# design.net
KiCad netlist of a schematic drawn in Altium Designer
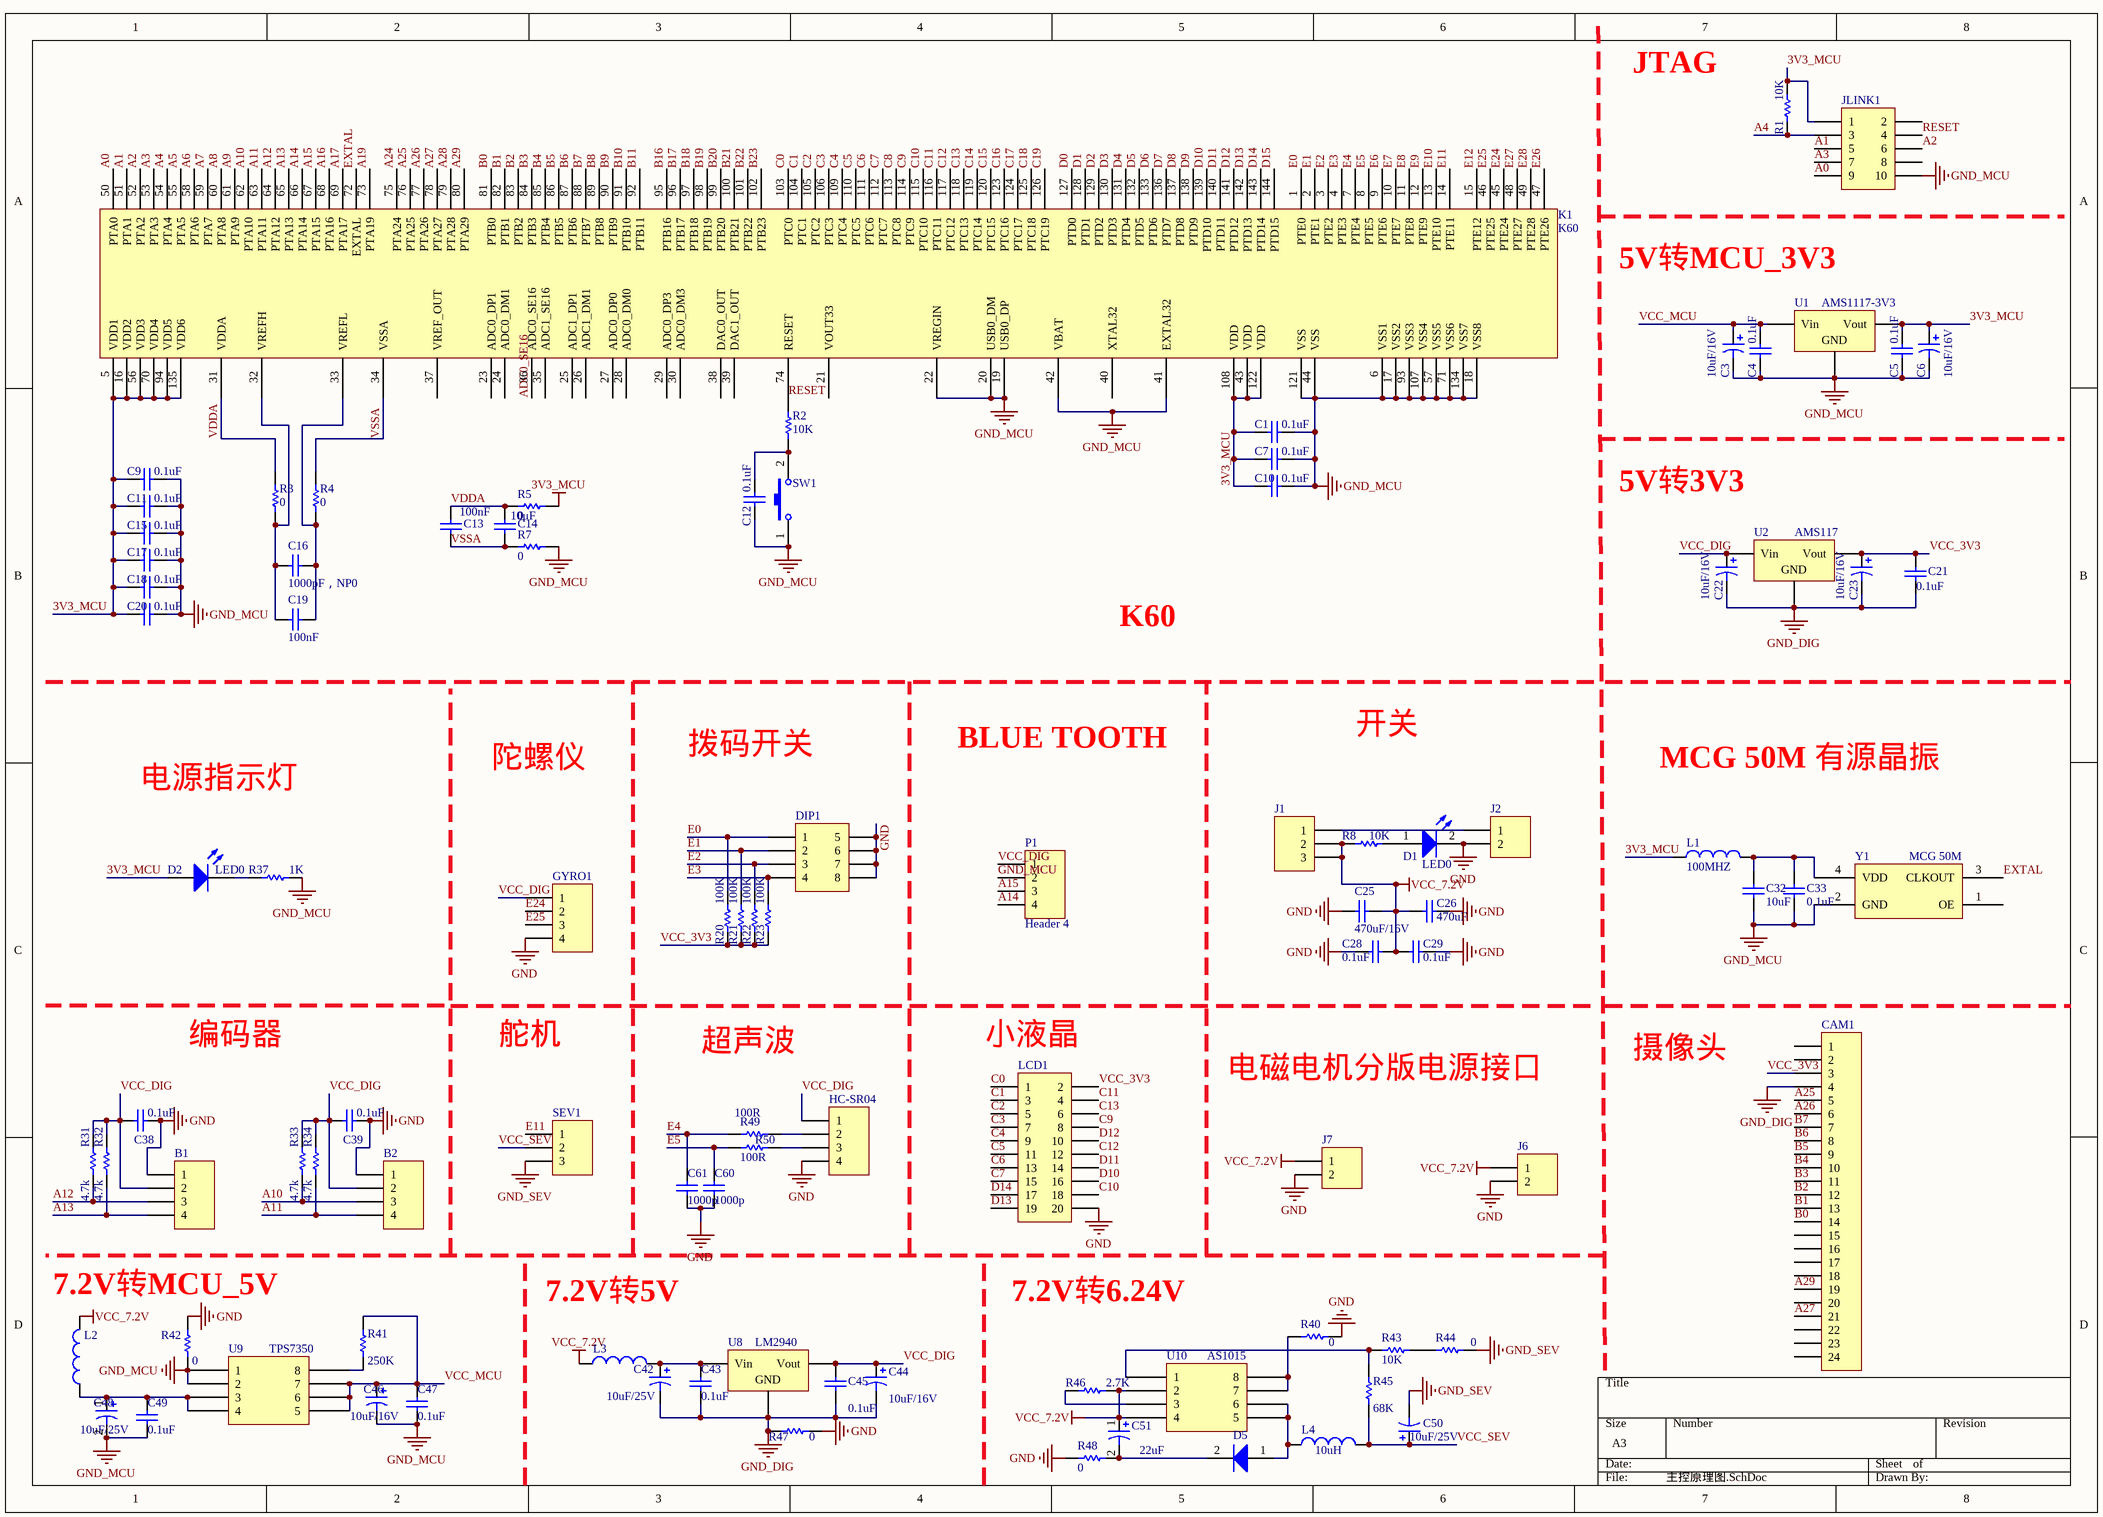
[diagram p0: 主控原理图.SchDoc]

(export (version "E")
  (design (tool "Eeschema 10.0.6"))
  (components
    (comp (ref "B1")
      (value "MHDR1X4")
      (footprint "3PIN-2.54")
      (description "Header, 4-Pin")
      (fields (field (name "PUBLISHER") "Altium Limited"))
      (libsource (lib "Miscellaneous Connectors") (part "MHDR1X4"))
    )
    (comp (ref "B2")
      (value "MHDR1X4")
      (footprint "3PIN-2.54")
      (description "Header, 4-Pin")
      (fields (field (name "PUBLISHER") "Altium Limited"))
      (libsource (lib "Miscellaneous Connectors") (part "MHDR1X4"))
    )
    (comp (ref "C1")
      (value "0.1uF")
      (footprint "c0805")
      (description "Capacitor")
      (fields (field (name "PUBLISHER") "Altium Limited"))
      (libsource (lib "Miscellaneous Devices") (part "Cap"))
    )
    (comp (ref "C3")
      (value "10uF/16V")
      (footprint "C1206")
      (description "Polarized Capacitor (Radial)")
      (fields (field (name "PUBLISHER") "Altium Limited"))
      (libsource (lib "") (part "Cap Pol1_1"))
    )
    (comp (ref "C4")
      (value "0.1uF")
      (footprint "c0805")
      (description "Capacitor")
      (fields (field (name "PUBLISHER") "Altium Limited"))
      (libsource (lib "Miscellaneous Devices") (part "Cap"))
    )
    (comp (ref "C5")
      (value "0.1uF")
      (footprint "c0805")
      (description "Capacitor")
      (fields (field (name "PUBLISHER") "Altium Limited"))
      (libsource (lib "Miscellaneous Devices") (part "Cap"))
    )
    (comp (ref "C6")
      (value "10uF/16V")
      (footprint "C1206")
      (description "Polarized Capacitor (Radial)")
      (fields (field (name "PUBLISHER") "Altium Limited"))
      (libsource (lib "") (part "Cap Pol1_1"))
    )
    (comp (ref "C7")
      (value "0.1uF")
      (footprint "c0805")
      (description "Capacitor")
      (fields (field (name "PUBLISHER") "Altium Limited"))
      (libsource (lib "Miscellaneous Devices") (part "Cap"))
    )
    (comp (ref "C9")
      (value "0.1uF")
      (footprint "c0805")
      (description "Capacitor")
      (fields (field (name "PUBLISHER") "Altium Limited"))
      (libsource (lib "Miscellaneous Devices") (part "Cap"))
    )
    (comp (ref "C10")
      (value "0.1uF")
      (footprint "c0805")
      (description "Capacitor")
      (fields (field (name "PUBLISHER") "Altium Limited"))
      (libsource (lib "Miscellaneous Devices") (part "Cap"))
    )
    (comp (ref "C11")
      (value "0.1uF")
      (footprint "c0805")
      (description "Capacitor")
      (fields (field (name "PUBLISHER") "Altium Limited"))
      (libsource (lib "Miscellaneous Devices") (part "Cap"))
    )
    (comp (ref "C12")
      (value "0.1uF")
      (footprint "c0805")
      (description "Capacitor")
      (fields (field (name "PUBLISHER") "Altium Limited"))
      (libsource (lib "Miscellaneous Devices") (part "Cap"))
    )
    (comp (ref "C13")
      (value "100nF")
      (footprint "C0805")
      (description "Capacitor (Semiconductor SIM Model)")
      (fields (field (name "Comment") "Cap Semi") (field (name "PUBLISHER") "Altium Limited"))
      (libsource (lib "Miscellaneous Devices") (part "Cap Semi"))
    )
    (comp (ref "C14")
      (value "10μF")
      (footprint "C0805")
      (description "Capacitor (Semiconductor SIM Model)")
      (fields (field (name "PUBLISHER") "Altium Limited"))
      (libsource (lib "Miscellaneous Devices") (part "Cap Semi"))
    )
    (comp (ref "C15")
      (value "0.1uF")
      (footprint "c0805")
      (description "Capacitor")
      (fields (field (name "PUBLISHER") "Altium Limited"))
      (libsource (lib "Miscellaneous Devices") (part "Cap"))
    )
    (comp (ref "C16")
      (value "1000pF，NP0")
      (footprint "C0805")
      (description "Capacitor (Semiconductor SIM Model)")
      (fields (field (name "Comment") "Cap Semi") (field (name "PUBLISHER") "Altium Limited"))
      (libsource (lib "Miscellaneous Devices") (part "Cap Semi"))
    )
    (comp (ref "C17")
      (value "0.1uF")
      (footprint "c0805")
      (description "Capacitor")
      (fields (field (name "PUBLISHER") "Altium Limited"))
      (libsource (lib "Miscellaneous Devices") (part "Cap"))
    )
    (comp (ref "C18")
      (value "0.1uF")
      (footprint "c0805")
      (description "Capacitor")
      (fields (field (name "PUBLISHER") "Altium Limited"))
      (libsource (lib "Miscellaneous Devices") (part "Cap"))
    )
    (comp (ref "C19")
      (value "100nF")
      (footprint "C0805")
      (description "Capacitor (Semiconductor SIM Model)")
      (fields (field (name "Comment") "Cap Semi") (field (name "PUBLISHER") "Altium Limited"))
      (libsource (lib "Miscellaneous Devices") (part "Cap Semi"))
    )
    (comp (ref "C20")
      (value "0.1uF")
      (footprint "c0805")
      (description "Capacitor")
      (fields (field (name "PUBLISHER") "Altium Limited"))
      (libsource (lib "Miscellaneous Devices") (part "Cap"))
    )
    (comp (ref "C21")
      (value "0.1uF")
      (footprint "C0805")
      (description "Capacitor")
      (fields (field (name "PUBLISHER") "Altium Limited"))
      (libsource (lib "Miscellaneous Devices") (part "Cap"))
    )
    (comp (ref "C22")
      (value "10uF/16V")
      (footprint "C1206")
      (description "Polarized Capacitor (Radial)")
      (fields (field (name "PUBLISHER") "Altium Limited"))
      (libsource (lib "") (part "Cap Pol1_1"))
    )
    (comp (ref "C23")
      (value "10uF/16V")
      (footprint "C1206")
      (description "Polarized Capacitor (Radial)")
      (fields (field (name "PUBLISHER") "Altium Limited"))
      (libsource (lib "") (part "Cap Pol1_1"))
    )
    (comp (ref "C25")
      (value "470uF/16V")
      (footprint "C8X8MM")
      (description "Capacitor")
      (fields (field (name "PUBLISHER") "Altium Limited"))
      (libsource (lib "Miscellaneous Devices") (part "Cap"))
    )
    (comp (ref "C26")
      (value "470uF")
      (footprint "C8X8MM")
      (description "Capacitor")
      (fields (field (name "Comment") "470uF/16V") (field (name "PUBLISHER") "Altium Limited"))
      (libsource (lib "Miscellaneous Devices") (part "Cap"))
    )
    (comp (ref "C28")
      (value "0.1uF")
      (footprint "C0805")
      (description "Capacitor")
      (fields (field (name "PUBLISHER") "Altium Limited"))
      (libsource (lib "Miscellaneous Devices") (part "Cap"))
    )
    (comp (ref "C29")
      (value "0.1uF")
      (footprint "C0805")
      (description "Capacitor")
      (fields (field (name "PUBLISHER") "Altium Limited"))
      (libsource (lib "Miscellaneous Devices") (part "Cap"))
    )
    (comp (ref "C32")
      (value "10uF")
      (footprint "c0805")
      (description "Capacitor")
      (fields (field (name "PUBLISHER") "Altium Limited"))
      (libsource (lib "Miscellaneous Devices") (part "Cap"))
    )
    (comp (ref "C33")
      (value "0.1uF")
      (footprint "c0805")
      (description "Capacitor")
      (fields (field (name "PUBLISHER") "Altium Limited"))
      (libsource (lib "Miscellaneous Devices") (part "Cap"))
    )
    (comp (ref "C38")
      (value "0.1uF")
      (footprint "C0805")
      (description "Capacitor")
      (fields (field (name "PUBLISHER") "Altium Limited"))
      (libsource (lib "Miscellaneous Devices") (part "Cap"))
    )
    (comp (ref "C39")
      (value "0.1uF")
      (footprint "C0805")
      (description "Capacitor")
      (fields (field (name "PUBLISHER") "Altium Limited"))
      (libsource (lib "Miscellaneous Devices") (part "Cap"))
    )
    (comp (ref "C42")
      (value "10uF/25V")
      (footprint "C1206")
      (description "Polarized Capacitor (Radial)")
      (fields (field (name "PUBLISHER") "Altium Limited"))
      (libsource (lib "") (part "Cap Pol1_1"))
    )
    (comp (ref "C43")
      (value "0.1uF")
      (footprint "C0805")
      (description "Capacitor")
      (fields (field (name "PUBLISHER") "Altium Limited"))
      (libsource (lib "Miscellaneous Devices") (part "Cap"))
    )
    (comp (ref "C44")
      (value "10uF/16V")
      (footprint "C1206")
      (description "Polarized Capacitor (Radial)")
      (fields (field (name "PUBLISHER") "Altium Limited"))
      (libsource (lib "") (part "Cap Pol1_1"))
    )
    (comp (ref "C45")
      (value "0.1uF")
      (footprint "C0805")
      (description "Capacitor")
      (fields (field (name "PUBLISHER") "Altium Limited"))
      (libsource (lib "Miscellaneous Devices") (part "Cap"))
    )
    (comp (ref "C46")
      (value "10uF/16V")
      (footprint "C1206")
      (description "Polarized Capacitor (Radial)")
      (fields (field (name "PUBLISHER") "Altium Limited"))
      (libsource (lib "") (part "Cap Pol1_1"))
    )
    (comp (ref "C47")
      (value "0.1uF")
      (footprint "C0805")
      (description "Capacitor")
      (fields (field (name "PUBLISHER") "Altium Limited"))
      (libsource (lib "Miscellaneous Devices") (part "Cap"))
    )
    (comp (ref "C48")
      (value "10uF/25V")
      (footprint "C1206")
      (description "Polarized Capacitor (Radial)")
      (fields (field (name "PUBLISHER") "Altium Limited"))
      (libsource (lib "Miscellaneous Devices") (part "Cap Pol1"))
    )
    (comp (ref "C49")
      (value "0.1uF")
      (footprint "C0805")
      (description "Capacitor")
      (fields (field (name "PUBLISHER") "Altium Limited"))
      (libsource (lib "Miscellaneous Devices") (part "Cap"))
    )
    (comp (ref "C50")
      (value "10uF/25V")
      (footprint "PCBComponent_1 - duplicate6")
      (description "Polarized Capacitor (Radial)")
      (fields (field (name "PUBLISHER") "Altium Limited"))
      (libsource (lib "") (part "Cap Pol1_1"))
    )
    (comp (ref "C51")
      (value "22uF")
      (footprint "CAP5X5")
      (description "Polarized Capacitor (Radial)")
      (fields (field (name "PUBLISHER") "Altium Limited"))
      (libsource (lib "Miscellaneous Devices") (part "Cap Pol1"))
    )
    (comp (ref "C60")
      (value "1000p")
      (footprint "C0805")
      (description "Capacitor")
      (fields (field (name "Comment") "0.1uF") (field (name "PUBLISHER") "Altium Limited"))
      (libsource (lib "Miscellaneous Devices") (part "Cap"))
    )
    (comp (ref "C61")
      (value "1000p")
      (footprint "C0805")
      (description "Capacitor")
      (fields (field (name "Comment") "0.1uF") (field (name "PUBLISHER") "Altium Limited"))
      (libsource (lib "Miscellaneous Devices") (part "Cap"))
    )
    (comp (ref "CAM1")
      (value "Header 24")
      (footprint "24PIN0.5MM软排座")
      (description "Header, 24-Pin")
      (fields (field (name "PUBLISHER") "Altium Limited"))
      (libsource (lib "Miscellaneous Connectors") (part "Header 24"))
    )
    (comp (ref "D1")
      (value "LED0")
      (footprint "d0603")
      (description "Typical INFRARED GaAs LED")
      (fields (field (name "PUBLISHER") "Altium Limited"))
      (libsource (lib "Miscellaneous Devices") (part "LED0"))
    )
    (comp (ref "D2")
      (value "LED0")
      (footprint "d0603")
      (description "Typical INFRARED GaAs LED")
      (fields (field (name "PUBLISHER") "Altium Limited"))
      (libsource (lib "") (part "LED0_1"))
    )
    (comp (ref "D5")
      (value "Diode 1N914")
      (footprint "四代目:SMA")
      (description "High Conductance Fast Diode")
      (fields (field (name "PUBLISHER") "Altium Limited"))
      (libsource (lib "Miscellaneous Devices") (part "Diode 1N914"))
    )
    (comp (ref "DIP1")
      (value "Header 4X2")
      (footprint "PCBComponent_1 - duplicate1")
      (description "Header, 4-Pin, Dual row")
      (fields (field (name "PUBLISHER") "Altium Limited"))
      (libsource (lib "Miscellaneous Connectors") (part "Header 4X2"))
    )
    (comp (ref "GYRO1")
      (value "Header 4")
      (footprint "tly")
      (description "Header, 4-Pin")
      (fields (field (name "PUBLISHER") "Altium Limited"))
      (libsource (lib "Miscellaneous Connectors") (part "Header 4"))
    )
    (comp (ref "HC-SR04")
      (value "Header 4")
      (footprint "SIP4")
      (description "Header, 4-Pin")
      (fields (field (name "PUBLISHER") "Altium Limited"))
      (libsource (lib "Miscellaneous Connectors") (part "Header 4"))
    )
    (comp (ref "J1")
      (value "Header 3")
      (footprint "7.2")
      (description "Header, 3-Pin")
      (fields (field (name "PUBLISHER") "Altium Limited"))
      (libsource (lib "") (part "Header 3_1"))
    )
    (comp (ref "J2")
      (value "Header 2")
      (footprint "PCBComponent_1 - duplicate5")
      (description "Header, 2-Pin")
      (fields (field (name "PUBLISHER") "Altium Limited"))
      (libsource (lib "Miscellaneous Connectors") (part "Header 2"))
    )
    (comp (ref "J6")
      (value "Header 2")
      (footprint "PCBComponent_1 - duplicate5")
      (description "Header, 2-Pin")
      (fields (field (name "PUBLISHER") "Altium Limited"))
      (libsource (lib "Miscellaneous Connectors") (part "Header 2"))
    )
    (comp (ref "J7")
      (value "Header 2")
      (footprint "PCBComponent_1 - duplicate5")
      (description "Header, 2-Pin")
      (fields (field (name "PUBLISHER") "Altium Limited"))
      (libsource (lib "Miscellaneous Connectors") (part "Header 2"))
    )
    (comp (ref "JLINK1")
      (value "Header 5X2")
      (footprint "HDR2X5")
      (description "Header, 5-Pin, Dual row")
      (fields (field (name "PUBLISHER") "Altium Limited"))
      (libsource (lib "Miscellaneous Connectors") (part "Header 5X2"))
    )
    (comp (ref "K1") (value "K60") (footprint "K60_QFP144") (libsource (lib "K60") (part "Component_1")))
    (comp (ref "L1")
      (value "100MHZ")
      (footprint "l0805")
      (description "Inductor")
      (fields (field (name "PUBLISHER") "Altium Limited"))
      (libsource (lib "Miscellaneous Devices") (part "Inductor"))
    )
    (comp (ref "L2")
      (value "~")
      (footprint "L0805")
      (description "Inductor")
      (fields (field (name "PUBLISHER") "Altium Limited"))
      (libsource (lib "Miscellaneous Devices") (part "Inductor"))
    )
    (comp (ref "L3")
      (value "Inductor")
      (footprint "L0805")
      (fields (field (name "PUBLISHER") "Altium Limited"))
      (libsource (lib "Miscellaneous Devices") (part "Inductor"))
    )
    (comp (ref "L4")
      (value "10uH")
      (footprint "电感7x7")
      (description "Inductor")
      (fields (field (name "PUBLISHER") "Altium Limited"))
      (libsource (lib "Miscellaneous Devices") (part "Inductor"))
    )
    (comp (ref "LCD1")
      (value "Header 10X2")
      (footprint "HDR2X10")
      (description "Header, 10-Pin, Dual row")
      (fields (field (name "PUBLISHER") "Altium Limited"))
      (libsource (lib "Miscellaneous Connectors") (part "Header 10X2"))
    )
    (comp (ref "P1")
      (value "Header 4")
      (footprint "HDR1X4")
      (description "Header, 4-Pin")
      (fields (field (name "PUBLISHER") "Altium Limited"))
      (libsource (lib "Miscellaneous Connectors") (part "Header 4"))
    )
    (comp (ref "R1")
      (value "10K")
      (footprint "R0805")
      (description "Resistor")
      (fields (field (name "PUBLISHER") "Altium Limited"))
      (libsource (lib "Miscellaneous Devices") (part "Res1"))
    )
    (comp (ref "R2")
      (value "10K")
      (footprint "r0805")
      (description "Resistor")
      (fields (field (name "PUBLISHER") "Altium Limited"))
      (libsource (lib "Miscellaneous Devices") (part "Res1"))
    )
    (comp (ref "R3")
      (value "0")
      (footprint "R0805")
      (description "Resistor")
      (fields (field (name "PUBLISHER") "Altium Limited"))
      (libsource (lib "Miscellaneous Devices") (part "Res1"))
    )
    (comp (ref "R4")
      (value "0")
      (footprint "R0805")
      (description "Resistor")
      (fields (field (name "PUBLISHER") "Altium Limited"))
      (libsource (lib "Miscellaneous Devices") (part "Res1"))
    )
    (comp (ref "R5")
      (value "0")
      (footprint "R0805")
      (description "Resistor")
      (fields (field (name "PUBLISHER") "Altium Limited"))
      (libsource (lib "Miscellaneous Devices") (part "Res1"))
    )
    (comp (ref "R7")
      (value "0")
      (footprint "R0805")
      (description "Resistor")
      (fields (field (name "PUBLISHER") "Altium Limited"))
      (libsource (lib "Miscellaneous Devices") (part "Res1"))
    )
    (comp (ref "R8")
      (value "10K")
      (footprint "R0805")
      (description "Resistor")
      (fields (field (name "Comment") "Res1") (field (name "PUBLISHER") "Altium Limited"))
      (libsource (lib "Miscellaneous Devices") (part "Res1"))
    )
    (comp (ref "R20")
      (value "100K")
      (footprint "R0805")
      (description "Resistor")
      (fields (field (name "PUBLISHER") "Altium Limited"))
      (libsource (lib "Miscellaneous Devices") (part "Res1"))
    )
    (comp (ref "R21")
      (value "100K")
      (footprint "R0805")
      (description "Resistor")
      (fields (field (name "PUBLISHER") "Altium Limited"))
      (libsource (lib "Miscellaneous Devices") (part "Res1"))
    )
    (comp (ref "R22")
      (value "100K")
      (footprint "R0805")
      (description "Resistor")
      (fields (field (name "PUBLISHER") "Altium Limited"))
      (libsource (lib "Miscellaneous Devices") (part "Res1"))
    )
    (comp (ref "R23")
      (value "100K")
      (footprint "R0805")
      (description "Resistor")
      (fields (field (name "PUBLISHER") "Altium Limited"))
      (libsource (lib "Miscellaneous Devices") (part "Res1"))
    )
    (comp (ref "R31")
      (value "4.7k")
      (footprint "R0805")
      (description "Resistor")
      (fields (field (name "Comment") "4.7K") (field (name "PUBLISHER") "Altium Limited"))
      (libsource (lib "Miscellaneous Devices") (part "Res1"))
    )
    (comp (ref "R32")
      (value "4.7k")
      (footprint "R0805")
      (description "Resistor")
      (fields (field (name "Comment") "4.7K") (field (name "PUBLISHER") "Altium Limited"))
      (libsource (lib "Miscellaneous Devices") (part "Res1"))
    )
    (comp (ref "R33")
      (value "4.7k")
      (footprint "R0805")
      (description "Resistor")
      (fields (field (name "Comment") "4.7K") (field (name "PUBLISHER") "Altium Limited"))
      (libsource (lib "Miscellaneous Devices") (part "Res1"))
    )
    (comp (ref "R34")
      (value "4.7k")
      (footprint "R0805")
      (description "Resistor")
      (fields (field (name "Comment") "4.7K") (field (name "PUBLISHER") "Altium Limited"))
      (libsource (lib "Miscellaneous Devices") (part "Res1"))
    )
    (comp (ref "R37")
      (value "1K")
      (footprint "R0805")
      (description "Resistor")
      (fields (field (name "PUBLISHER") "Altium Limited"))
      (libsource (lib "Miscellaneous Devices") (part "Res1"))
    )
    (comp (ref "R40")
      (value "0")
      (footprint "R0805")
      (description "Resistor")
      (fields (field (name "PUBLISHER") "Altium Limited"))
      (libsource (lib "Miscellaneous Devices") (part "Res1"))
    )
    (comp (ref "R41")
      (value "250K")
      (footprint "R0805")
      (description "Resistor")
      (fields (field (name "PUBLISHER") "Altium Limited"))
      (libsource (lib "Miscellaneous Devices") (part "Res1"))
    )
    (comp (ref "R42")
      (value "0")
      (footprint "R0805")
      (description "Resistor")
      (fields (field (name "PUBLISHER") "Altium Limited"))
      (libsource (lib "Miscellaneous Devices") (part "Res1"))
    )
    (comp (ref "R43")
      (value "10K")
      (footprint "R0805")
      (description "Resistor")
      (fields (field (name "PUBLISHER") "Altium Limited"))
      (libsource (lib "Miscellaneous Devices") (part "Res1"))
    )
    (comp (ref "R44")
      (value "0")
      (footprint "R0805")
      (description "Resistor")
      (fields (field (name "PUBLISHER") "Altium Limited"))
      (libsource (lib "Miscellaneous Devices") (part "Res1"))
    )
    (comp (ref "R45")
      (value "68K")
      (footprint "R0805")
      (description "Resistor")
      (fields (field (name "PUBLISHER") "Altium Limited"))
      (libsource (lib "Miscellaneous Devices") (part "Res1"))
    )
    (comp (ref "R46")
      (value "2.7K")
      (footprint "R0805")
      (description "Resistor")
      (fields (field (name "PUBLISHER") "Altium Limited"))
      (libsource (lib "Miscellaneous Devices") (part "Res1"))
    )
    (comp (ref "R47")
      (value "0")
      (footprint "R0805")
      (description "Resistor")
      (fields (field (name "PUBLISHER") "Altium Limited"))
      (libsource (lib "Miscellaneous Devices") (part "Res1"))
    )
    (comp (ref "R48")
      (value "0")
      (footprint "R0805")
      (description "Resistor")
      (fields (field (name "PUBLISHER") "Altium Limited"))
      (libsource (lib "Miscellaneous Devices") (part "Res1"))
    )
    (comp (ref "R49")
      (value "100R")
      (footprint "R0805")
      (description "Resistor")
      (fields (field (name "Comment") "100K") (field (name "PUBLISHER") "Altium Limited"))
      (libsource (lib "Miscellaneous Devices") (part "Res1"))
    )
    (comp (ref "R50")
      (value "100R")
      (footprint "R0805")
      (description "Resistor")
      (fields (field (name "Comment") "100K") (field (name "PUBLISHER") "Altium Limited"))
      (libsource (lib "Miscellaneous Devices") (part "Res1"))
    )
    (comp (ref "SEV1")
      (value "Header 3")
      (footprint "SIP3")
      (description "Header, 3-Pin")
      (fields (field (name "PUBLISHER") "Altium Limited"))
      (libsource (lib "Miscellaneous Connectors") (part "Header 3"))
    )
    (comp (ref "SW1")
      (value "SW-PB")
      (footprint "四代目:key")
      (description "Switch")
      (fields (field (name "PUBLISHER") "Altium Limited"))
      (libsource (lib "Miscellaneous Devices") (part "SW-PB"))
    )
    (comp (ref "U1")
      (value "AMS1117-3V3")
      (footprint "SOT-223")
      (description "Voltage Regulator")
      (fields (field (name "PUBLISHER") "Altium Limited"))
      (libsource (lib "Miscellaneous Devices") (part "Volt Reg"))
    )
    (comp (ref "U2")
      (value "AMS117")
      (footprint "SOT-223")
      (description "Voltage Regulator")
      (fields (field (name "PUBLISHER") "Altium Limited"))
      (libsource (lib "Miscellaneous Devices") (part "Volt Reg"))
    )
    (comp (ref "U8")
      (value "LM2940")
      (footprint "TO263")
      (description "Voltage Regulator")
      (fields (field (name "PUBLISHER") "Altium Limited"))
      (libsource (lib "") (part "Volt Reg_1"))
    )
    (comp (ref "U9") (value "TPS7350") (footprint "sop8") (libsource (lib "Schlib1") (part "Component_1")))
    (comp (ref "U10")
      (value "AS1015")
      (footprint "四代目:sop8")
      (libsource (lib "Schlib1") (part "Component_1"))
    )
    (comp (ref "Y1") (value "MCG 50M") (footprint "四代目:MCG") (libsource (lib "K60") (part "Component_2")))
  )
  (nets
    (net (code "1") (name "/A0") (class "Default")
      (node (ref "JLINK1") (pin "9") (pinfunction "9_9") (pintype "passive"))
      (node (ref "K1") (pin "50") (pinfunction "PTA0_50") (pintype "passive"))
    )
    (net (code "2") (name "/A1") (class "Default")
      (node (ref "JLINK1") (pin "5") (pinfunction "5_5") (pintype "passive"))
      (node (ref "K1") (pin "51") (pinfunction "PTA1_51") (pintype "passive"))
    )
    (net (code "3") (name "/A2") (class "Default")
      (node (ref "JLINK1") (pin "6") (pinfunction "6_6") (pintype "passive"))
      (node (ref "K1") (pin "52") (pinfunction "PTA2_52") (pintype "passive"))
    )
    (net (code "4") (name "/A3") (class "Default")
      (node (ref "JLINK1") (pin "7") (pinfunction "7_7") (pintype "passive"))
      (node (ref "K1") (pin "53") (pinfunction "PTA3_53") (pintype "passive"))
    )
    (net (code "5") (name "/A4") (class "Default")
      (node (ref "JLINK1") (pin "3") (pinfunction "3_3") (pintype "passive"))
      (node (ref "K1") (pin "54") (pinfunction "PTA4_54") (pintype "passive"))
      (node (ref "R1") (pin "1") (pinfunction "1_1") (pintype "passive"))
    )
    (net (code "6") (name "/A5") (class "Default")
      (node (ref "K1") (pin "55") (pinfunction "PTA5_55") (pintype "passive"))
    )
    (net (code "7") (name "/A6") (class "Default")
      (node (ref "K1") (pin "58") (pinfunction "PTA6_58") (pintype "passive"))
    )
    (net (code "8") (name "/A7") (class "Default")
      (node (ref "K1") (pin "59") (pinfunction "PTA7_59") (pintype "passive"))
    )
    (net (code "9") (name "/A8") (class "Default")
      (node (ref "K1") (pin "60") (pinfunction "PTA8_60") (pintype "passive"))
    )
    (net (code "10") (name "/A9") (class "Default")
      (node (ref "K1") (pin "61") (pinfunction "PTA9_61") (pintype "passive"))
    )
    (net (code "11") (name "/A10") (class "Default")
      (node (ref "B2") (pin "3") (pinfunction "3_3") (pintype "passive"))
      (node (ref "K1") (pin "62") (pinfunction "PTA10_62") (pintype "passive"))
      (node (ref "R33") (pin "1") (pinfunction "1_1") (pintype "passive"))
    )
    (net (code "12") (name "/A11") (class "Default")
      (node (ref "B2") (pin "4") (pinfunction "4_4") (pintype "passive"))
      (node (ref "K1") (pin "63") (pinfunction "PTA11_63") (pintype "passive"))
      (node (ref "R34") (pin "1") (pinfunction "1_1") (pintype "passive"))
    )
    (net (code "13") (name "/A12") (class "Default")
      (node (ref "B1") (pin "3") (pinfunction "3_3") (pintype "passive"))
      (node (ref "K1") (pin "64") (pinfunction "PTA12_64") (pintype "passive"))
      (node (ref "R31") (pin "1") (pinfunction "1_1") (pintype "passive"))
    )
    (net (code "14") (name "/A13") (class "Default")
      (node (ref "B1") (pin "4") (pinfunction "4_4") (pintype "passive"))
      (node (ref "K1") (pin "65") (pinfunction "PTA13_65") (pintype "passive"))
      (node (ref "R32") (pin "1") (pinfunction "1_1") (pintype "passive"))
    )
    (net (code "15") (name "/A14") (class "Default")
      (node (ref "K1") (pin "66") (pinfunction "PTA14_66") (pintype "passive"))
      (node (ref "P1") (pin "4") (pinfunction "4_4") (pintype "passive"))
    )
    (net (code "16") (name "/A15") (class "Default")
      (node (ref "K1") (pin "67") (pinfunction "PTA15_67") (pintype "passive"))
      (node (ref "P1") (pin "3") (pinfunction "3_3") (pintype "passive"))
    )
    (net (code "17") (name "/A16") (class "Default")
      (node (ref "K1") (pin "68") (pinfunction "PTA16_68") (pintype "passive"))
    )
    (net (code "18") (name "/A17") (class "Default")
      (node (ref "K1") (pin "69") (pinfunction "PTA17_69") (pintype "passive"))
    )
    (net (code "19") (name "/A19") (class "Default")
      (node (ref "K1") (pin "73") (pinfunction "PTA19_73") (pintype "passive"))
    )
    (net (code "20") (name "/A24") (class "Default")
      (node (ref "K1") (pin "75") (pinfunction "PTA24_75") (pintype "passive"))
    )
    (net (code "21") (name "/A25") (class "Default")
      (node (ref "CAM1") (pin "5") (pinfunction "5_5") (pintype "passive"))
      (node (ref "K1") (pin "76") (pinfunction "PTA25_76") (pintype "passive"))
    )
    (net (code "22") (name "/A26") (class "Default")
      (node (ref "CAM1") (pin "6") (pinfunction "6_6") (pintype "passive"))
      (node (ref "K1") (pin "77") (pinfunction "PTA26_77") (pintype "passive"))
    )
    (net (code "23") (name "/A27") (class "Default")
      (node (ref "CAM1") (pin "21") (pinfunction "21_21") (pintype "passive"))
      (node (ref "K1") (pin "78") (pinfunction "PTA27_78") (pintype "passive"))
    )
    (net (code "24") (name "/A28") (class "Default")
      (node (ref "K1") (pin "79") (pinfunction "PTA28_79") (pintype "passive"))
    )
    (net (code "25") (name "/A29") (class "Default")
      (node (ref "CAM1") (pin "19") (pinfunction "19_19") (pintype "passive"))
      (node (ref "K1") (pin "80") (pinfunction "PTA29_80") (pintype "passive"))
    )
    (net (code "26") (name "/ADC0_SE16") (class "Default")
      (node (ref "K1") (pin "36") (pinfunction "ADC0_SE16_36") (pintype "passive"))
    )
    (net (code "27") (name "/B0") (class "Default")
      (node (ref "CAM1") (pin "14") (pinfunction "14_14") (pintype "passive"))
      (node (ref "K1") (pin "81") (pinfunction "PTB0_81") (pintype "passive"))
    )
    (net (code "28") (name "/B1") (class "Default")
      (node (ref "CAM1") (pin "13") (pinfunction "13_13") (pintype "passive"))
      (node (ref "K1") (pin "82") (pinfunction "PTB1_82") (pintype "passive"))
    )
    (net (code "29") (name "/B2") (class "Default")
      (node (ref "CAM1") (pin "12") (pinfunction "12_12") (pintype "passive"))
      (node (ref "K1") (pin "83") (pinfunction "PTB2_83") (pintype "passive"))
    )
    (net (code "30") (name "/B3") (class "Default")
      (node (ref "CAM1") (pin "11") (pinfunction "11_11") (pintype "passive"))
      (node (ref "K1") (pin "84") (pinfunction "PTB3_84") (pintype "passive"))
    )
    (net (code "31") (name "/B4") (class "Default")
      (node (ref "CAM1") (pin "10") (pinfunction "10_10") (pintype "passive"))
      (node (ref "K1") (pin "85") (pinfunction "PTB4_85") (pintype "passive"))
    )
    (net (code "32") (name "/B5") (class "Default")
      (node (ref "CAM1") (pin "9") (pinfunction "9_9") (pintype "passive"))
      (node (ref "K1") (pin "86") (pinfunction "PTB5_86") (pintype "passive"))
    )
    (net (code "33") (name "/B6") (class "Default")
      (node (ref "CAM1") (pin "8") (pinfunction "8_8") (pintype "passive"))
      (node (ref "K1") (pin "87") (pinfunction "PTB6_87") (pintype "passive"))
    )
    (net (code "34") (name "/B7") (class "Default")
      (node (ref "CAM1") (pin "7") (pinfunction "7_7") (pintype "passive"))
      (node (ref "K1") (pin "88") (pinfunction "PTB7_88") (pintype "passive"))
    )
    (net (code "35") (name "/B8") (class "Default")
      (node (ref "K1") (pin "89") (pinfunction "PTB8_89") (pintype "passive"))
    )
    (net (code "36") (name "/B9") (class "Default")
      (node (ref "K1") (pin "90") (pinfunction "PTB9_90") (pintype "passive"))
    )
    (net (code "37") (name "/B10") (class "Default")
      (node (ref "K1") (pin "91") (pinfunction "PTB10_91") (pintype "passive"))
    )
    (net (code "38") (name "/B11") (class "Default")
      (node (ref "K1") (pin "92") (pinfunction "PTB11_92") (pintype "passive"))
    )
    (net (code "39") (name "/B16") (class "Default")
      (node (ref "K1") (pin "95") (pinfunction "PTB16_95") (pintype "passive"))
    )
    (net (code "40") (name "/B17") (class "Default")
      (node (ref "K1") (pin "96") (pinfunction "PTB17_96") (pintype "passive"))
    )
    (net (code "41") (name "/B18") (class "Default")
      (node (ref "K1") (pin "97") (pinfunction "PTB18_97") (pintype "passive"))
    )
    (net (code "42") (name "/B19") (class "Default")
      (node (ref "K1") (pin "98") (pinfunction "PTB19_98") (pintype "passive"))
    )
    (net (code "43") (name "/B20") (class "Default")
      (node (ref "K1") (pin "99") (pinfunction "PTB20_99") (pintype "passive"))
    )
    (net (code "44") (name "/B21") (class "Default")
      (node (ref "K1") (pin "100") (pinfunction "PTB21_100") (pintype "passive"))
    )
    (net (code "45") (name "/B22") (class "Default")
      (node (ref "K1") (pin "101") (pinfunction "PTB22_101") (pintype "passive"))
    )
    (net (code "46") (name "/B23") (class "Default")
      (node (ref "K1") (pin "102") (pinfunction "PTB23_102") (pintype "passive"))
    )
    (net (code "47") (name "/C0") (class "Default")
      (node (ref "K1") (pin "103") (pinfunction "PTC0_103") (pintype "passive"))
      (node (ref "LCD1") (pin "1") (pinfunction "1_1") (pintype "passive"))
    )
    (net (code "48") (name "/C1") (class "Default")
      (node (ref "K1") (pin "104") (pinfunction "PTC1_104") (pintype "passive"))
      (node (ref "LCD1") (pin "3") (pinfunction "3_3") (pintype "passive"))
    )
    (net (code "49") (name "/C2") (class "Default")
      (node (ref "K1") (pin "105") (pinfunction "PTC2_105") (pintype "passive"))
      (node (ref "LCD1") (pin "5") (pinfunction "5_5") (pintype "passive"))
    )
    (net (code "50") (name "/C3") (class "Default")
      (node (ref "K1") (pin "106") (pinfunction "PTC3_106") (pintype "passive"))
      (node (ref "LCD1") (pin "7") (pinfunction "7_7") (pintype "passive"))
    )
    (net (code "51") (name "/C4") (class "Default")
      (node (ref "K1") (pin "109") (pinfunction "PTC4_109") (pintype "passive"))
      (node (ref "LCD1") (pin "9") (pinfunction "9_9") (pintype "passive"))
    )
    (net (code "52") (name "/C5") (class "Default")
      (node (ref "K1") (pin "110") (pinfunction "PTC5_110") (pintype "passive"))
      (node (ref "LCD1") (pin "11") (pinfunction "11_11") (pintype "passive"))
    )
    (net (code "53") (name "/C6") (class "Default")
      (node (ref "K1") (pin "111") (pinfunction "PTC6_111") (pintype "passive"))
      (node (ref "LCD1") (pin "13") (pinfunction "13_13") (pintype "passive"))
    )
    (net (code "54") (name "/C7") (class "Default")
      (node (ref "K1") (pin "112") (pinfunction "PTC7_112") (pintype "passive"))
      (node (ref "LCD1") (pin "15") (pinfunction "15_15") (pintype "passive"))
    )
    (net (code "55") (name "/C8") (class "Default")
      (node (ref "K1") (pin "113") (pinfunction "PTC8_113") (pintype "passive"))
    )
    (net (code "56") (name "/C9") (class "Default")
      (node (ref "K1") (pin "114") (pinfunction "PTC9_114") (pintype "passive"))
      (node (ref "LCD1") (pin "8") (pinfunction "8_8") (pintype "passive"))
    )
    (net (code "57") (name "/C10") (class "Default")
      (node (ref "K1") (pin "115") (pinfunction "PTC10_115") (pintype "passive"))
      (node (ref "LCD1") (pin "18") (pinfunction "18_18") (pintype "passive"))
    )
    (net (code "58") (name "/C11") (class "Default")
      (node (ref "K1") (pin "116") (pinfunction "PTC11_116") (pintype "passive"))
      (node (ref "LCD1") (pin "4") (pinfunction "4_4") (pintype "passive"))
    )
    (net (code "59") (name "/C12") (class "Default")
      (node (ref "K1") (pin "117") (pinfunction "PTC12_117") (pintype "passive"))
      (node (ref "LCD1") (pin "12") (pinfunction "12_12") (pintype "passive"))
    )
    (net (code "60") (name "/C13") (class "Default")
      (node (ref "K1") (pin "118") (pinfunction "PTC13_118") (pintype "passive"))
      (node (ref "LCD1") (pin "6") (pinfunction "6_6") (pintype "passive"))
    )
    (net (code "61") (name "/C14") (class "Default")
      (node (ref "K1") (pin "119") (pinfunction "PTC14_119") (pintype "passive"))
    )
    (net (code "62") (name "/C15") (class "Default")
      (node (ref "K1") (pin "120") (pinfunction "PTC15_120") (pintype "passive"))
    )
    (net (code "63") (name "/C16") (class "Default")
      (node (ref "K1") (pin "123") (pinfunction "PTC16_123") (pintype "passive"))
    )
    (net (code "64") (name "/C17") (class "Default")
      (node (ref "K1") (pin "124") (pinfunction "PTC17_124") (pintype "passive"))
    )
    (net (code "65") (name "/C18") (class "Default")
      (node (ref "K1") (pin "125") (pinfunction "PTC18_125") (pintype "passive"))
    )
    (net (code "66") (name "/C19") (class "Default")
      (node (ref "K1") (pin "126") (pinfunction "PTC19_126") (pintype "passive"))
    )
    (net (code "67") (name "/D0") (class "Default")
      (node (ref "K1") (pin "127") (pinfunction "PTD0_127") (pintype "passive"))
    )
    (net (code "68") (name "/D1") (class "Default")
      (node (ref "K1") (pin "128") (pinfunction "PTD1_128") (pintype "passive"))
    )
    (net (code "69") (name "/D2") (class "Default")
      (node (ref "K1") (pin "129") (pinfunction "PTD2_129") (pintype "passive"))
    )
    (net (code "70") (name "/D3") (class "Default")
      (node (ref "K1") (pin "130") (pinfunction "PTD3_130") (pintype "passive"))
    )
    (net (code "71") (name "/D4") (class "Default")
      (node (ref "K1") (pin "131") (pinfunction "PTD4_131") (pintype "passive"))
    )
    (net (code "72") (name "/D5") (class "Default")
      (node (ref "K1") (pin "132") (pinfunction "PTD5_132") (pintype "passive"))
    )
    (net (code "73") (name "/D6") (class "Default")
      (node (ref "K1") (pin "133") (pinfunction "PTD6_133") (pintype "passive"))
    )
    (net (code "74") (name "/D7") (class "Default")
      (node (ref "K1") (pin "136") (pinfunction "PTD7_136") (pintype "passive"))
    )
    (net (code "75") (name "/D8") (class "Default")
      (node (ref "K1") (pin "137") (pinfunction "PTD8_137") (pintype "passive"))
    )
    (net (code "76") (name "/D9") (class "Default")
      (node (ref "K1") (pin "138") (pinfunction "PTD9_138") (pintype "passive"))
    )
    (net (code "77") (name "/D10") (class "Default")
      (node (ref "K1") (pin "139") (pinfunction "PTD10_139") (pintype "passive"))
      (node (ref "LCD1") (pin "16") (pinfunction "16_16") (pintype "passive"))
    )
    (net (code "78") (name "/D11") (class "Default")
      (node (ref "K1") (pin "140") (pinfunction "PTD11_140") (pintype "passive"))
      (node (ref "LCD1") (pin "14") (pinfunction "14_14") (pintype "passive"))
    )
    (net (code "79") (name "/D12") (class "Default")
      (node (ref "K1") (pin "141") (pinfunction "PTD12_141") (pintype "passive"))
      (node (ref "LCD1") (pin "10") (pinfunction "10_10") (pintype "passive"))
    )
    (net (code "80") (name "/D13") (class "Default")
      (node (ref "K1") (pin "142") (pinfunction "PTD13_142") (pintype "passive"))
      (node (ref "LCD1") (pin "19") (pinfunction "19_19") (pintype "passive"))
    )
    (net (code "81") (name "/D14") (class "Default")
      (node (ref "K1") (pin "143") (pinfunction "PTD14_143") (pintype "passive"))
      (node (ref "LCD1") (pin "17") (pinfunction "17_17") (pintype "passive"))
    )
    (net (code "82") (name "/D15") (class "Default")
      (node (ref "K1") (pin "144") (pinfunction "PTD15_144") (pintype "passive"))
    )
    (net (code "83") (name "/E0") (class "Default")
      (node (ref "DIP1") (pin "1") (pinfunction "1_1") (pintype "passive"))
      (node (ref "K1") (pin "1") (pinfunction "PTE0_1") (pintype "passive"))
      (node (ref "R20") (pin "2") (pinfunction "2_2") (pintype "passive"))
    )
    (net (code "84") (name "/E1") (class "Default")
      (node (ref "DIP1") (pin "2") (pinfunction "2_2") (pintype "passive"))
      (node (ref "K1") (pin "2") (pinfunction "PTE1_2") (pintype "passive"))
      (node (ref "R21") (pin "2") (pinfunction "2_2") (pintype "passive"))
    )
    (net (code "85") (name "/E2") (class "Default")
      (node (ref "DIP1") (pin "3") (pinfunction "3_3") (pintype "passive"))
      (node (ref "K1") (pin "3") (pinfunction "PTE2_3") (pintype "passive"))
      (node (ref "R22") (pin "2") (pinfunction "2_2") (pintype "passive"))
    )
    (net (code "86") (name "/E3") (class "Default")
      (node (ref "DIP1") (pin "4") (pinfunction "4_4") (pintype "passive"))
      (node (ref "K1") (pin "4") (pinfunction "PTE3_4") (pintype "passive"))
      (node (ref "R23") (pin "2") (pinfunction "2_2") (pintype "passive"))
    )
    (net (code "87") (name "/E4") (class "Default")
      (node (ref "C61") (pin "2") (pinfunction "2_2") (pintype "passive"))
      (node (ref "K1") (pin "7") (pinfunction "PTE4_7") (pintype "passive"))
      (node (ref "R49") (pin "1") (pinfunction "1_1") (pintype "passive"))
    )
    (net (code "88") (name "/E5") (class "Default")
      (node (ref "C60") (pin "2") (pinfunction "2_2") (pintype "passive"))
      (node (ref "K1") (pin "8") (pinfunction "PTE5_8") (pintype "passive"))
      (node (ref "R50") (pin "1") (pinfunction "1_1") (pintype "passive"))
    )
    (net (code "89") (name "/E6") (class "Default")
      (node (ref "K1") (pin "9") (pinfunction "PTE6_9") (pintype "passive"))
    )
    (net (code "90") (name "/E7") (class "Default")
      (node (ref "K1") (pin "10") (pinfunction "PTE7_10") (pintype "passive"))
    )
    (net (code "91") (name "/E8") (class "Default")
      (node (ref "K1") (pin "11") (pinfunction "PTE8_11") (pintype "passive"))
    )
    (net (code "92") (name "/E9") (class "Default")
      (node (ref "K1") (pin "12") (pinfunction "PTE9_12") (pintype "passive"))
    )
    (net (code "93") (name "/E10") (class "Default")
      (node (ref "K1") (pin "13") (pinfunction "PTE10_13") (pintype "passive"))
    )
    (net (code "94") (name "/E11") (class "Default")
      (node (ref "K1") (pin "14") (pinfunction "PTE11_14") (pintype "passive"))
      (node (ref "SEV1") (pin "1") (pinfunction "1_1") (pintype "passive"))
    )
    (net (code "95") (name "/E12") (class "Default")
      (node (ref "K1") (pin "15") (pinfunction "PTE12_15") (pintype "passive"))
    )
    (net (code "96") (name "/E24") (class "Default")
      (node (ref "GYRO1") (pin "2") (pinfunction "2_2") (pintype "passive"))
      (node (ref "K1") (pin "45") (pinfunction "PTE24_45") (pintype "passive"))
    )
    (net (code "97") (name "/E25") (class "Default")
      (node (ref "GYRO1") (pin "3") (pinfunction "3_3") (pintype "passive"))
      (node (ref "K1") (pin "46") (pinfunction "PTE25_46") (pintype "passive"))
    )
    (net (code "98") (name "/E26") (class "Default")
      (node (ref "K1") (pin "47") (pinfunction "PTE26_47") (pintype "passive"))
    )
    (net (code "99") (name "/E27") (class "Default")
      (node (ref "K1") (pin "48") (pinfunction "PTE27_48") (pintype "passive"))
    )
    (net (code "100") (name "/E28") (class "Default")
      (node (ref "K1") (pin "49") (pinfunction "PTE28_49") (pintype "passive"))
    )
    (net (code "101") (name "/EXTAL") (class "Default")
      (node (ref "K1") (pin "72") (pinfunction "EXTAL_72") (pintype "passive"))
      (node (ref "Y1") (pin "3") (pinfunction "CLKOUT_3") (pintype "passive"))
    )
    (net (code "102") (name "/RESET") (class "Default")
      (node (ref "JLINK1") (pin "4") (pinfunction "4_4") (pintype "passive"))
      (node (ref "K1") (pin "74") (pinfunction "RESET_74") (pintype "passive"))
      (node (ref "R2") (pin "2") (pinfunction "2_2") (pintype "passive"))
    )
    (net (code "103") (name "/VCC_3V3") (class "Default")
      (node (ref "C21") (pin "2") (pinfunction "2_2") (pintype "passive"))
      (node (ref "C23") (pin "1") (pinfunction "1_1") (pintype "passive"))
      (node (ref "CAM1") (pin "3") (pinfunction "3_3") (pintype "passive"))
      (node (ref "LCD1") (pin "2") (pinfunction "2_2") (pintype "passive"))
      (node (ref "R20") (pin "1") (pinfunction "1_1") (pintype "passive"))
      (node (ref "R21") (pin "1") (pinfunction "1_1") (pintype "passive"))
      (node (ref "R22") (pin "1") (pinfunction "1_1") (pintype "passive"))
      (node (ref "R23") (pin "1") (pinfunction "1_1") (pintype "passive"))
      (node (ref "U2") (pin "2") (pinfunction "Vout_2") (pintype "passive"))
    )
    (net (code "104") (name "/VCC_DIG") (class "Default")
      (node (ref "B1") (pin "2") (pinfunction "2_2") (pintype "passive"))
      (node (ref "B2") (pin "2") (pinfunction "2_2") (pintype "passive"))
      (node (ref "C22") (pin "1") (pinfunction "1_1") (pintype "passive"))
      (node (ref "C38") (pin "1") (pinfunction "1_1") (pintype "passive"))
      (node (ref "C39") (pin "1") (pinfunction "1_1") (pintype "passive"))
      (node (ref "C44") (pin "1") (pinfunction "1_1") (pintype "passive"))
      (node (ref "C45") (pin "2") (pinfunction "2_2") (pintype "passive"))
      (node (ref "GYRO1") (pin "1") (pinfunction "1_1") (pintype "passive"))
      (node (ref "HC-SR04") (pin "1") (pinfunction "1_1") (pintype "passive"))
      (node (ref "P1") (pin "1") (pinfunction "1_1") (pintype "passive"))
      (node (ref "R31") (pin "2") (pinfunction "2_2") (pintype "passive"))
      (node (ref "R32") (pin "2") (pinfunction "2_2") (pintype "passive"))
      (node (ref "R33") (pin "2") (pinfunction "2_2") (pintype "passive"))
      (node (ref "R34") (pin "2") (pinfunction "2_2") (pintype "passive"))
      (node (ref "U2") (pin "3") (pinfunction "Vin_3") (pintype "passive"))
      (node (ref "U8") (pin "3") (pinfunction "Vout_3") (pintype "passive"))
    )
    (net (code "105") (name "/VCC_MCU") (class "Default")
      (node (ref "C3") (pin "1") (pinfunction "1_1") (pintype "passive"))
      (node (ref "C4") (pin "2") (pinfunction "2_2") (pintype "passive"))
      (node (ref "C46") (pin "1") (pinfunction "1_1") (pintype "passive"))
      (node (ref "C47") (pin "2") (pinfunction "2_2") (pintype "passive"))
      (node (ref "R41") (pin "2") (pinfunction "2_2") (pintype "passive"))
      (node (ref "U1") (pin "3") (pinfunction "Vin_3") (pintype "passive"))
      (node (ref "U9") (pin "5") (pinfunction "5_5") (pintype "passive"))
      (node (ref "U9") (pin "6") (pinfunction "6_6") (pintype "passive"))
      (node (ref "U9") (pin "7") (pinfunction "7_7") (pintype "passive"))
    )
    (net (code "106") (name "/VCC_SEV") (class "Default")
      (node (ref "C50") (pin "1") (pinfunction "1_1") (pintype "passive"))
      (node (ref "L4") (pin "2") (pinfunction "2_2") (pintype "passive"))
      (node (ref "R45") (pin "1") (pinfunction "1_1") (pintype "passive"))
      (node (ref "SEV1") (pin "2") (pinfunction "2_2") (pintype "passive"))
    )
    (net (code "107") (name "/VDDA") (class "Default")
      (node (ref "C13") (pin "2") (pinfunction "2_2") (pintype "passive"))
      (node (ref "C14") (pin "2") (pinfunction "2_2") (pintype "passive"))
      (node (ref "K1") (pin "31") (pinfunction "VDDA_31") (pintype "passive"))
      (node (ref "R3") (pin "2") (pinfunction "2_2") (pintype "passive"))
      (node (ref "R5") (pin "2") (pinfunction "2_2") (pintype "passive"))
    )
    (net (code "108") (name "/VSSA") (class "Default")
      (node (ref "C13") (pin "1") (pinfunction "1_1") (pintype "passive"))
      (node (ref "C14") (pin "1") (pinfunction "1_1") (pintype "passive"))
      (node (ref "K1") (pin "34") (pinfunction "VSSA_34") (pintype "passive"))
      (node (ref "R4") (pin "2") (pinfunction "2_2") (pintype "passive"))
      (node (ref "R7") (pin "2") (pinfunction "2_2") (pintype "passive"))
    )
    (net (code "109") (name "3V3_MCU") (class "Default")
      (node (ref "C1") (pin "2") (pinfunction "2_2") (pintype "passive"))
      (node (ref "C10") (pin "2") (pinfunction "2_2") (pintype "passive"))
      (node (ref "C11") (pin "1") (pinfunction "1_1") (pintype "passive"))
      (node (ref "C15") (pin "1") (pinfunction "1_1") (pintype "passive"))
      (node (ref "C17") (pin "1") (pinfunction "1_1") (pintype "passive"))
      (node (ref "C18") (pin "1") (pinfunction "1_1") (pintype "passive"))
      (node (ref "C20") (pin "1") (pinfunction "1_1") (pintype "passive"))
      (node (ref "C5") (pin "2") (pinfunction "2_2") (pintype "passive"))
      (node (ref "C6") (pin "1") (pinfunction "1_1") (pintype "passive"))
      (node (ref "C7") (pin "2") (pinfunction "2_2") (pintype "passive"))
      (node (ref "C9") (pin "1") (pinfunction "1_1") (pintype "passive"))
      (node (ref "D2") (pin "1") (pinfunction "A_1") (pintype "passive"))
      (node (ref "JLINK1") (pin "1") (pinfunction "1_1") (pintype "passive"))
      (node (ref "K1") (pin "108") (pinfunction "VDD_108") (pintype "passive"))
      (node (ref "K1") (pin "122") (pinfunction "VDD_122") (pintype "passive"))
      (node (ref "K1") (pin "135") (pinfunction "VDD6_135") (pintype "passive"))
      (node (ref "K1") (pin "16") (pinfunction "VDD2_16") (pintype "passive"))
      (node (ref "K1") (pin "43") (pinfunction "VDD_43") (pintype "passive"))
      (node (ref "K1") (pin "5") (pinfunction "VDD1_5") (pintype "passive"))
      (node (ref "K1") (pin "56") (pinfunction "VDD3_56") (pintype "passive"))
      (node (ref "K1") (pin "70") (pinfunction "VDD4_70") (pintype "passive"))
      (node (ref "K1") (pin "94") (pinfunction "VDD5_94") (pintype "passive"))
      (node (ref "L1") (pin "1") (pinfunction "1_1") (pintype "passive"))
      (node (ref "R1") (pin "2") (pinfunction "2_2") (pintype "passive"))
      (node (ref "R5") (pin "1") (pinfunction "1_1") (pintype "passive"))
      (node (ref "U1") (pin "2") (pinfunction "Vout_2") (pintype "passive"))
    )
    (net (code "110") (name "GND") (class "Default")
      (node (ref "B1") (pin "1") (pinfunction "1_1") (pintype "passive"))
      (node (ref "B2") (pin "1") (pinfunction "1_1") (pintype "passive"))
      (node (ref "C25") (pin "2") (pinfunction "2_2") (pintype "passive"))
      (node (ref "C26") (pin "2") (pinfunction "2_2") (pintype "passive"))
      (node (ref "C28") (pin "1") (pinfunction "1_1") (pintype "passive"))
      (node (ref "C29") (pin "2") (pinfunction "2_2") (pintype "passive"))
      (node (ref "C38") (pin "2") (pinfunction "2_2") (pintype "passive"))
      (node (ref "C39") (pin "2") (pinfunction "2_2") (pintype "passive"))
      (node (ref "C60") (pin "1") (pinfunction "1_1") (pintype "passive"))
      (node (ref "C61") (pin "1") (pinfunction "1_1") (pintype "passive"))
      (node (ref "D1") (pin "2") (pinfunction "K_2") (pintype "passive"))
      (node (ref "DIP1") (pin "5") (pinfunction "5_5") (pintype "passive"))
      (node (ref "DIP1") (pin "6") (pinfunction "6_6") (pintype "passive"))
      (node (ref "DIP1") (pin "7") (pinfunction "7_7") (pintype "passive"))
      (node (ref "DIP1") (pin "8") (pinfunction "8_8") (pintype "passive"))
      (node (ref "GYRO1") (pin "4") (pinfunction "4_4") (pintype "passive"))
      (node (ref "HC-SR04") (pin "4") (pinfunction "4_4") (pintype "passive"))
      (node (ref "J2") (pin "2") (pinfunction "2_2") (pintype "passive"))
      (node (ref "J6") (pin "2") (pinfunction "2_2") (pintype "passive"))
      (node (ref "J7") (pin "2") (pinfunction "2_2") (pintype "passive"))
      (node (ref "LCD1") (pin "20") (pinfunction "20_20") (pintype "passive"))
      (node (ref "R40") (pin "2") (pinfunction "2_2") (pintype "passive"))
      (node (ref "R42") (pin "2") (pinfunction "2_2") (pintype "passive"))
      (node (ref "R47") (pin "2") (pinfunction "2_2") (pintype "passive"))
      (node (ref "R48") (pin "2") (pinfunction "2_2") (pintype "passive"))
    )
    (net (code "111") (name "GND_DIG") (class "Default")
      (node (ref "C21") (pin "1") (pinfunction "1_1") (pintype "passive"))
      (node (ref "C22") (pin "2") (pinfunction "2_2") (pintype "passive"))
      (node (ref "C23") (pin "2") (pinfunction "2_2") (pintype "passive"))
      (node (ref "C42") (pin "2") (pinfunction "2_2") (pintype "passive"))
      (node (ref "C43") (pin "1") (pinfunction "1_1") (pintype "passive"))
      (node (ref "C44") (pin "2") (pinfunction "2_2") (pintype "passive"))
      (node (ref "C45") (pin "1") (pinfunction "1_1") (pintype "passive"))
      (node (ref "CAM1") (pin "4") (pinfunction "4_4") (pintype "passive"))
      (node (ref "R47") (pin "1") (pinfunction "1_1") (pintype "passive"))
      (node (ref "U2") (pin "1") (pinfunction "GND_1") (pintype "passive"))
      (node (ref "U8") (pin "2") (pinfunction "GND_2") (pintype "passive"))
    )
    (net (code "112") (name "GND_MCU") (class "Default")
      (node (ref "C1") (pin "1") (pinfunction "1_1") (pintype "passive"))
      (node (ref "C10") (pin "1") (pinfunction "1_1") (pintype "passive"))
      (node (ref "C11") (pin "2") (pinfunction "2_2") (pintype "passive"))
      (node (ref "C12") (pin "1") (pinfunction "1_1") (pintype "passive"))
      (node (ref "C15") (pin "2") (pinfunction "2_2") (pintype "passive"))
      (node (ref "C17") (pin "2") (pinfunction "2_2") (pintype "passive"))
      (node (ref "C18") (pin "2") (pinfunction "2_2") (pintype "passive"))
      (node (ref "C20") (pin "2") (pinfunction "2_2") (pintype "passive"))
      (node (ref "C3") (pin "2") (pinfunction "2_2") (pintype "passive"))
      (node (ref "C32") (pin "1") (pinfunction "1_1") (pintype "passive"))
      (node (ref "C33") (pin "1") (pinfunction "1_1") (pintype "passive"))
      (node (ref "C4") (pin "1") (pinfunction "1_1") (pintype "passive"))
      (node (ref "C46") (pin "2") (pinfunction "2_2") (pintype "passive"))
      (node (ref "C47") (pin "1") (pinfunction "1_1") (pintype "passive"))
      (node (ref "C48") (pin "2") (pinfunction "2_2") (pintype "passive"))
      (node (ref "C49") (pin "1") (pinfunction "1_1") (pintype "passive"))
      (node (ref "C5") (pin "1") (pinfunction "1_1") (pintype "passive"))
      (node (ref "C6") (pin "2") (pinfunction "2_2") (pintype "passive"))
      (node (ref "C7") (pin "1") (pinfunction "1_1") (pintype "passive"))
      (node (ref "C9") (pin "2") (pinfunction "2_2") (pintype "passive"))
      (node (ref "JLINK1") (pin "10") (pinfunction "10_10") (pintype "passive"))
      (node (ref "K1") (pin "107") (pinfunction "VSS4_107") (pintype "passive"))
      (node (ref "K1") (pin "121") (pinfunction "VSS_121") (pintype "passive"))
      (node (ref "K1") (pin "134") (pinfunction "VSS7_134") (pintype "passive"))
      (node (ref "K1") (pin "17") (pinfunction "VSS2_17") (pintype "passive"))
      (node (ref "K1") (pin "18") (pinfunction "VSS8_18") (pintype "passive"))
      (node (ref "K1") (pin "19") (pinfunction "USB0_DP_19") (pintype "passive"))
      (node (ref "K1") (pin "20") (pinfunction "USB0_DM_20") (pintype "passive"))
      (node (ref "K1") (pin "22") (pinfunction "VREGIN_22") (pintype "passive"))
      (node (ref "K1") (pin "41") (pinfunction "EXTAL32_41") (pintype "passive"))
      (node (ref "K1") (pin "42") (pinfunction "VBAT_42") (pintype "passive"))
      (node (ref "K1") (pin "44") (pinfunction "VSS_44") (pintype "passive"))
      (node (ref "K1") (pin "57") (pinfunction "VSS5_57") (pintype "passive"))
      (node (ref "K1") (pin "6") (pinfunction "VSS1_6") (pintype "passive"))
      (node (ref "K1") (pin "71") (pinfunction "VSS6_71") (pintype "passive"))
      (node (ref "K1") (pin "93") (pinfunction "VSS3_93") (pintype "passive"))
      (node (ref "P1") (pin "2") (pinfunction "2_2") (pintype "passive"))
      (node (ref "R37") (pin "2") (pinfunction "2_2") (pintype "passive"))
      (node (ref "R42") (pin "1") (pinfunction "1_1") (pintype "passive"))
      (node (ref "R7") (pin "1") (pinfunction "1_1") (pintype "passive"))
      (node (ref "SW1") (pin "1") (pinfunction "1_1") (pintype "passive"))
      (node (ref "U1") (pin "1") (pinfunction "GND_1") (pintype "passive"))
      (node (ref "U9") (pin "1") (pinfunction "1_1") (pintype "passive"))
      (node (ref "U9") (pin "2") (pinfunction "2_2") (pintype "passive"))
      (node (ref "Y1") (pin "2") (pinfunction "GND_2") (pintype "passive"))
    )
    (net (code "113") (name "GND_SEV") (class "Default")
      (node (ref "C50") (pin "2") (pinfunction "2_2") (pintype "passive"))
      (node (ref "R44") (pin "2") (pinfunction "2_2") (pintype "passive"))
      (node (ref "SEV1") (pin "3") (pinfunction "3_3") (pintype "passive"))
    )
    (net (code "114") (name "Net-(C12-Pad2)") (class "Default")
      (node (ref "C12") (pin "2") (pinfunction "2_2") (pintype "passive"))
      (node (ref "R2") (pin "1") (pinfunction "1_1") (pintype "passive"))
      (node (ref "SW1") (pin "2") (pinfunction "2_2") (pintype "passive"))
    )
    (net (code "115") (name "Net-(C48-Pad1)") (class "Default")
      (node (ref "C48") (pin "1") (pinfunction "1_1") (pintype "passive"))
      (node (ref "C49") (pin "2") (pinfunction "2_2") (pintype "passive"))
      (node (ref "L2") (pin "1") (pinfunction "1_1") (pintype "passive"))
      (node (ref "U9") (pin "3") (pinfunction "3_3") (pintype "passive"))
      (node (ref "U9") (pin "4") (pinfunction "4_4") (pintype "passive"))
    )
    (net (code "116") (name "Net-(C51-Pad2)") (class "Default")
      (node (ref "C51") (pin "2") (pinfunction "2_2") (pintype "passive"))
      (node (ref "D5") (pin "2") (pinfunction "2_2") (pintype "passive"))
      (node (ref "R48") (pin "1") (pinfunction "1_1") (pintype "passive"))
    )
    (net (code "117") (name "Net-(D1-A)") (class "Default")
      (node (ref "D1") (pin "1") (pinfunction "A_1") (pintype "passive"))
      (node (ref "R8") (pin "2") (pinfunction "2_2") (pintype "passive"))
    )
    (net (code "118") (name "Net-(D2-K)") (class "Default")
      (node (ref "D2") (pin "2") (pinfunction "K_2") (pintype "passive"))
      (node (ref "R37") (pin "1") (pinfunction "1_1") (pintype "passive"))
    )
    (net (code "119") (name "Net-(D5-Pad1)") (class "Default")
      (node (ref "D5") (pin "1") (pinfunction "1_1") (pintype "passive"))
      (node (ref "L4") (pin "1") (pinfunction "1_1") (pintype "passive"))
      (node (ref "U10") (pin "5") (pinfunction "5_5") (pintype "passive"))
      (node (ref "U10") (pin "6") (pinfunction "6_6") (pintype "passive"))
    )
    (net (code "120") (name "Net-(HC-SR04-Pad2)") (class "Default")
      (node (ref "HC-SR04") (pin "2") (pinfunction "2_2") (pintype "passive"))
      (node (ref "R49") (pin "2") (pinfunction "2_2") (pintype "passive"))
    )
    (net (code "121") (name "Net-(HC-SR04-Pad3)") (class "Default")
      (node (ref "HC-SR04") (pin "3") (pinfunction "3_3") (pintype "passive"))
      (node (ref "R50") (pin "2") (pinfunction "2_2") (pintype "passive"))
    )
    (net (code "122") (name "Net-(J1-Pad1)") (class "Default")
      (node (ref "J1") (pin "1") (pinfunction "1_1") (pintype "passive"))
      (node (ref "J2") (pin "1") (pinfunction "1_1") (pintype "passive"))
    )
    (net (code "123") (name "Net-(K1-VREFH)") (class "Default")
      (node (ref "C16") (pin "2") (pinfunction "2_2") (pintype "passive"))
      (node (ref "C19") (pin "2") (pinfunction "2_2") (pintype "passive"))
      (node (ref "K1") (pin "32") (pinfunction "VREFH_32") (pintype "passive"))
      (node (ref "R3") (pin "1") (pinfunction "1_1") (pintype "passive"))
    )
    (net (code "124") (name "Net-(K1-VREFL)") (class "Default")
      (node (ref "C16") (pin "1") (pinfunction "1_1") (pintype "passive"))
      (node (ref "C19") (pin "1") (pinfunction "1_1") (pintype "passive"))
      (node (ref "K1") (pin "33") (pinfunction "VREFL_33") (pintype "passive"))
      (node (ref "R4") (pin "1") (pinfunction "1_1") (pintype "passive"))
    )
    (net (code "125") (name "Net-(R40-Pad1)") (class "Default")
      (node (ref "R40") (pin "1") (pinfunction "1_1") (pintype "passive"))
      (node (ref "U10") (pin "7") (pinfunction "7_7") (pintype "passive"))
      (node (ref "U10") (pin "8") (pinfunction "8_8") (pintype "passive"))
    )
    (net (code "126") (name "Net-(R41-Pad1)") (class "Default")
      (node (ref "R41") (pin "1") (pinfunction "1_1") (pintype "passive"))
      (node (ref "U9") (pin "8") (pinfunction "8_8") (pintype "passive"))
    )
    (net (code "127") (name "Net-(R43-Pad1)") (class "Default")
      (node (ref "R43") (pin "1") (pinfunction "1_1") (pintype "passive"))
      (node (ref "R44") (pin "1") (pinfunction "1_1") (pintype "passive"))
    )
    (net (code "128") (name "Net-(R43-Pad2)") (class "Default")
      (node (ref "R43") (pin "2") (pinfunction "2_2") (pintype "passive"))
      (node (ref "R45") (pin "2") (pinfunction "2_2") (pintype "passive"))
      (node (ref "U10") (pin "1") (pinfunction "1_1") (pintype "passive"))
    )
    (net (code "129") (name "Net-(R46-Pad2)") (class "Default")
      (node (ref "R46") (pin "2") (pinfunction "2_2") (pintype "passive"))
      (node (ref "U10") (pin "3") (pinfunction "3_3") (pintype "passive"))
    )
    (net (code "130") (name "Net-(U8-Vin)") (class "Default")
      (node (ref "C42") (pin "1") (pinfunction "1_1") (pintype "passive"))
      (node (ref "C43") (pin "2") (pinfunction "2_2") (pintype "passive"))
      (node (ref "L3") (pin "2") (pinfunction "2_2") (pintype "passive"))
      (node (ref "U8") (pin "1") (pinfunction "Vin_1") (pintype "passive"))
    )
    (net (code "131") (name "Net-(Y1-VDD)") (class "Default")
      (node (ref "C32") (pin "2") (pinfunction "2_2") (pintype "passive"))
      (node (ref "C33") (pin "2") (pinfunction "2_2") (pintype "passive"))
      (node (ref "L1") (pin "2") (pinfunction "2_2") (pintype "passive"))
      (node (ref "Y1") (pin "4") (pinfunction "VDD_4") (pintype "passive"))
    )
    (net (code "132") (name "VCC_7.2V") (class "Default")
      (node (ref "C25") (pin "1") (pinfunction "1_1") (pintype "passive"))
      (node (ref "C26") (pin "1") (pinfunction "1_1") (pintype "passive"))
      (node (ref "C28") (pin "2") (pinfunction "2_2") (pintype "passive"))
      (node (ref "C29") (pin "1") (pinfunction "1_1") (pintype "passive"))
      (node (ref "C51") (pin "1") (pinfunction "1_1") (pintype "passive"))
      (node (ref "J1") (pin "2") (pinfunction "2_2") (pintype "passive"))
      (node (ref "J1") (pin "3") (pinfunction "3_3") (pintype "passive"))
      (node (ref "J6") (pin "1") (pinfunction "1_1") (pintype "passive"))
      (node (ref "J7") (pin "1") (pinfunction "1_1") (pintype "passive"))
      (node (ref "L2") (pin "2") (pinfunction "2_2") (pintype "passive"))
      (node (ref "L3") (pin "1") (pinfunction "1_1") (pintype "passive"))
      (node (ref "R46") (pin "1") (pinfunction "1_1") (pintype "passive"))
      (node (ref "R8") (pin "1") (pinfunction "1_1") (pintype "passive"))
      (node (ref "U10") (pin "2") (pinfunction "2_2") (pintype "passive"))
      (node (ref "U10") (pin "4") (pinfunction "4_4") (pintype "passive"))
    )
    (net (code "133") (name "unconnected-(CAM1-Pad1)") (class "Default")
      (node (ref "CAM1") (pin "1") (pinfunction "1_1") (pintype "passive"))
    )
    (net (code "134") (name "unconnected-(CAM1-Pad2)") (class "Default")
      (node (ref "CAM1") (pin "2") (pinfunction "2_2") (pintype "passive"))
    )
    (net (code "135") (name "unconnected-(CAM1-Pad15)") (class "Default")
      (node (ref "CAM1") (pin "15") (pinfunction "15_15") (pintype "passive"))
    )
    (net (code "136") (name "unconnected-(CAM1-Pad16)") (class "Default")
      (node (ref "CAM1") (pin "16") (pinfunction "16_16") (pintype "passive"))
    )
    (net (code "137") (name "unconnected-(CAM1-Pad17)") (class "Default")
      (node (ref "CAM1") (pin "17") (pinfunction "17_17") (pintype "passive"))
    )
    (net (code "138") (name "unconnected-(CAM1-Pad18)") (class "Default")
      (node (ref "CAM1") (pin "18") (pinfunction "18_18") (pintype "passive"))
    )
    (net (code "139") (name "unconnected-(CAM1-Pad20)") (class "Default")
      (node (ref "CAM1") (pin "20") (pinfunction "20_20") (pintype "passive"))
    )
    (net (code "140") (name "unconnected-(CAM1-Pad22)") (class "Default")
      (node (ref "CAM1") (pin "22") (pinfunction "22_22") (pintype "passive"))
    )
    (net (code "141") (name "unconnected-(CAM1-Pad23)") (class "Default")
      (node (ref "CAM1") (pin "23") (pinfunction "23_23") (pintype "passive"))
    )
    (net (code "142") (name "unconnected-(CAM1-Pad24)") (class "Default")
      (node (ref "CAM1") (pin "24") (pinfunction "24_24") (pintype "passive"))
    )
    (net (code "143") (name "unconnected-(JLINK1-Pad2)") (class "Default")
      (node (ref "JLINK1") (pin "2") (pinfunction "2_2") (pintype "passive"))
    )
    (net (code "144") (name "unconnected-(JLINK1-Pad8)") (class "Default")
      (node (ref "JLINK1") (pin "8") (pinfunction "8_8") (pintype "passive"))
    )
    (net (code "145") (name "unconnected-(K1-ADC0_DM0-Pad28)") (class "Default")
      (node (ref "K1") (pin "28") (pinfunction "ADC0_DM0_28") (pintype "passive"))
    )
    (net (code "146") (name "unconnected-(K1-ADC0_DM1-Pad24)") (class "Default")
      (node (ref "K1") (pin "24") (pinfunction "ADC0_DM1_24") (pintype "passive"))
    )
    (net (code "147") (name "unconnected-(K1-ADC0_DM3-Pad30)") (class "Default")
      (node (ref "K1") (pin "30") (pinfunction "ADC0_DM3_30") (pintype "passive"))
    )
    (net (code "148") (name "unconnected-(K1-ADC0_DP0-Pad27)") (class "Default")
      (node (ref "K1") (pin "27") (pinfunction "ADC0_DP0_27") (pintype "passive"))
    )
    (net (code "149") (name "unconnected-(K1-ADC0_DP1-Pad23)") (class "Default")
      (node (ref "K1") (pin "23") (pinfunction "ADC0_DP1_23") (pintype "passive"))
    )
    (net (code "150") (name "unconnected-(K1-ADC0_DP3-Pad29)") (class "Default")
      (node (ref "K1") (pin "29") (pinfunction "ADC0_DP3_29") (pintype "passive"))
    )
    (net (code "151") (name "unconnected-(K1-ADC1_DM1-Pad26)") (class "Default")
      (node (ref "K1") (pin "26") (pinfunction "ADC1_DM1_26") (pintype "passive"))
    )
    (net (code "152") (name "unconnected-(K1-ADC1_DP1-Pad25)") (class "Default")
      (node (ref "K1") (pin "25") (pinfunction "ADC1_DP1_25") (pintype "passive"))
    )
    (net (code "153") (name "unconnected-(K1-ADC1_SE16-Pad35)") (class "Default")
      (node (ref "K1") (pin "35") (pinfunction "ADC1_SE16_35") (pintype "passive"))
    )
    (net (code "154") (name "unconnected-(K1-DAC0_OUT-Pad38)") (class "Default")
      (node (ref "K1") (pin "38") (pinfunction "DAC0_OUT_38") (pintype "passive"))
    )
    (net (code "155") (name "unconnected-(K1-DAC1_OUT-Pad39)") (class "Default")
      (node (ref "K1") (pin "39") (pinfunction "DAC1_OUT_39") (pintype "passive"))
    )
    (net (code "156") (name "unconnected-(K1-VOUT33-Pad21)") (class "Default")
      (node (ref "K1") (pin "21") (pinfunction "VOUT33_21") (pintype "passive"))
    )
    (net (code "157") (name "unconnected-(K1-VREF_OUT-Pad37)") (class "Default")
      (node (ref "K1") (pin "37") (pinfunction "VREF_OUT_37") (pintype "passive"))
    )
    (net (code "158") (name "unconnected-(K1-XTAL32-Pad40)") (class "Default")
      (node (ref "K1") (pin "40") (pinfunction "XTAL32_40") (pintype "passive"))
    )
    (net (code "159") (name "unconnected-(Y1-OE-Pad1)") (class "Default")
      (node (ref "Y1") (pin "1") (pinfunction "OE_1") (pintype "passive"))
    )
  )
)
